# ColorDetection.net
KiCad netlist of a schematic drawn in EAGLE
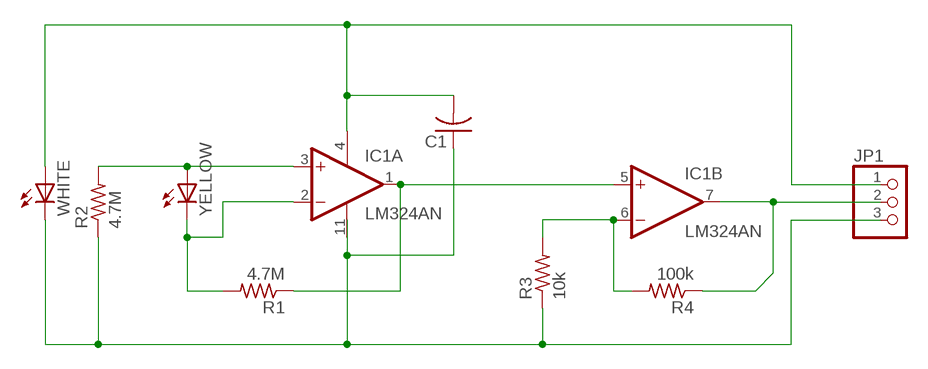
[diagram p0: schematic, sheet 1]

(export (version "E")
  (design (tool "Eeschema 10.0.6"))
  (components
    (comp (ref "C1")
      (value "C-USC0805")
      (footprint "eagle-import:C0805")
      (libsource (lib "eagle-import") (part "C-USC0805"))
    )
    (comp (ref "IC1")
      (value "LM324AN")
      (footprint "eagle-import:DIL14")
      (libsource (lib "eagle-import") (part "MCP604P"))
    )
    (comp (ref "JP1")
      (value "PINHD-1X3")
      (footprint "eagle-import:1X03")
      (libsource (lib "eagle-import") (part "PINHD-1X3"))
    )
    (comp (ref "R1")
      (value "4.7M")
      (footprint "eagle-import:M0805")
      (libsource (lib "eagle-import") (part "R-US_M0805"))
    )
    (comp (ref "R2")
      (value "4.7M")
      (footprint "eagle-import:M0805")
      (libsource (lib "eagle-import") (part "R-US_M0805"))
    )
    (comp (ref "R3")
      (value "10k")
      (footprint "eagle-import:M0805")
      (libsource (lib "eagle-import") (part "R-US_M0805"))
    )
    (comp (ref "R4")
      (value "100k")
      (footprint "eagle-import:M0805")
      (libsource (lib "eagle-import") (part "R-US_M0805"))
    )
    (comp (ref "WHITE")
      (value "LED10MM")
      (footprint "eagle-import:LED10MM")
      (libsource (lib "eagle-import") (part "LED10MM"))
    )
    (comp (ref "YELLOW")
      (value "LED5MM")
      (footprint "eagle-import:LED5MM")
      (libsource (lib "eagle-import") (part "LED5MM"))
    )
  )
  (nets
    (net (code "1") (name "/V-") (class "Default")
      (node (ref "IC1") (pin "11") (pinfunction "V-_11") (pintype "power_in"))
    )
    (net (code "2") (name "Net-(IC1A-+IN)") (class "Default")
      (node (ref "IC1") (pin "3") (pinfunction "+IN_3") (pintype "input"))
      (node (ref "R2") (pin "2") (pinfunction "2_2") (pintype "passive"))
      (node (ref "YELLOW") (pin "A") (pinfunction "A_A") (pintype "passive"))
    )
    (net (code "3") (name "Net-(IC1A--IN)") (class "Default")
      (node (ref "IC1") (pin "2") (pinfunction "-IN_2") (pintype "input"))
      (node (ref "R1") (pin "2") (pinfunction "2_2") (pintype "passive"))
      (node (ref "YELLOW") (pin "K") (pinfunction "C_K") (pintype "passive"))
    )
    (net (code "4") (name "Net-(IC1A-OUT)") (class "Default")
      (node (ref "IC1") (pin "1") (pinfunction "OUT_1") (pintype "output"))
      (node (ref "IC1") (pin "5") (pinfunction "+IN_5") (pintype "input"))
      (node (ref "R1") (pin "1") (pinfunction "1_1") (pintype "passive"))
    )
    (net (code "5") (name "Net-(IC1B--IN)") (class "Default")
      (node (ref "IC1") (pin "6") (pinfunction "-IN_6") (pintype "input"))
      (node (ref "R3") (pin "2") (pinfunction "2_2") (pintype "passive"))
      (node (ref "R4") (pin "2") (pinfunction "2_2") (pintype "passive"))
    )
    (net (code "6") (name "Net-(IC1B-OUT)") (class "Default")
      (node (ref "IC1") (pin "7") (pinfunction "OUT_7") (pintype "output"))
      (node (ref "JP1") (pin "2") (pinfunction "2_2") (pintype "passive"))
      (node (ref "R4") (pin "1") (pinfunction "1_1") (pintype "passive"))
    )
    (net (code "7") (name "Net-(IC1E-V+)") (class "Default")
      (node (ref "C1") (pin "2") (pinfunction "2_2") (pintype "passive"))
      (node (ref "IC1") (pin "4") (pinfunction "V+_4") (pintype "power_in"))
      (node (ref "JP1") (pin "1") (pinfunction "1_1") (pintype "passive"))
      (node (ref "WHITE") (pin "A") (pinfunction "A_A") (pintype "passive"))
    )
    (net (code "8") (name "Net-(WHITE-C)") (class "Default")
      (node (ref "C1") (pin "1") (pinfunction "1_1") (pintype "passive"))
      (node (ref "JP1") (pin "3") (pinfunction "3_3") (pintype "passive"))
      (node (ref "R2") (pin "1") (pinfunction "1_1") (pintype "passive"))
      (node (ref "R3") (pin "1") (pinfunction "1_1") (pintype "passive"))
      (node (ref "WHITE") (pin "K") (pinfunction "C_K") (pintype "passive"))
    )
  )
)
